# glove_final.net
KiCad netlist of a schematic drawn in EAGLE
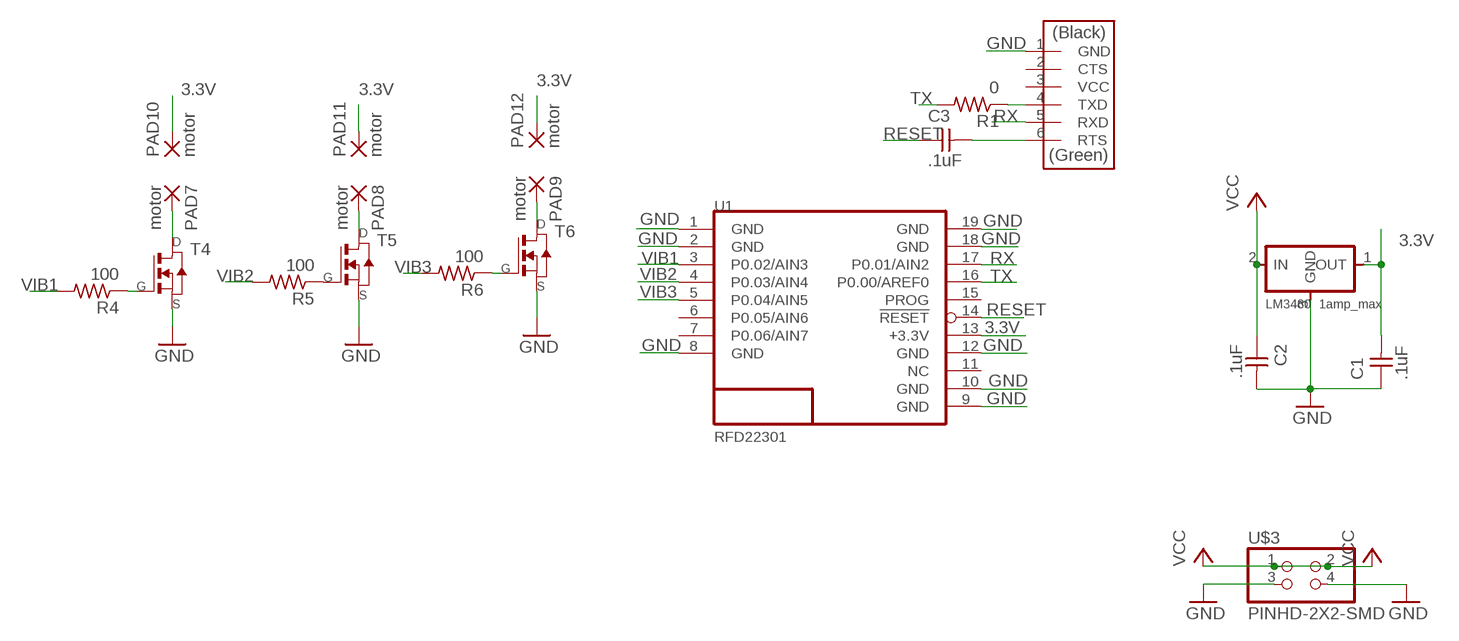
[diagram p0: schematic, sheet 1]

(export (version "E")
  (design (tool "Eeschema 10.0.6"))
  (components
    (comp (ref "C1")
      (value ".1uF")
      (footprint "eagle-import:C1206FAB")
      (libsource (lib "eagle-import") (part "CAP-UNPOLARIZEDFAB"))
    )
    (comp (ref "C2")
      (value ".1uF")
      (footprint "eagle-import:C1206FAB")
      (libsource (lib "eagle-import") (part "CAP-UNPOLARIZEDFAB"))
    )
    (comp (ref "C3")
      (value ".1uF")
      (footprint "eagle-import:C1206FAB")
      (libsource (lib "eagle-import") (part "CAP-UNPOLARIZEDFAB"))
    )
    (comp (ref "LM3480")
      (value "1amp_max")
      (footprint "eagle-import:SOT23")
      (libsource (lib "eagle-import") (part "REGULATORSOT23"))
    )
    (comp (ref "PAD7")
      (value "motor")
      (footprint "eagle-import:SMD1,27-2,54")
      (libsource (lib "eagle-import") (part "WIREPADSMD1,27-254"))
    )
    (comp (ref "PAD8")
      (value "motor")
      (footprint "eagle-import:SMD1,27-2,54")
      (libsource (lib "eagle-import") (part "WIREPADSMD1,27-254"))
    )
    (comp (ref "PAD9")
      (value "motor")
      (footprint "eagle-import:SMD1,27-2,54")
      (libsource (lib "eagle-import") (part "WIREPADSMD1,27-254"))
    )
    (comp (ref "PAD10")
      (value "motor")
      (footprint "eagle-import:SMD1,27-2,54")
      (libsource (lib "eagle-import") (part "WIREPADSMD1,27-254"))
    )
    (comp (ref "PAD11")
      (value "motor")
      (footprint "eagle-import:SMD1,27-2,54")
      (libsource (lib "eagle-import") (part "WIREPADSMD1,27-254"))
    )
    (comp (ref "PAD12")
      (value "motor")
      (footprint "eagle-import:SMD1,27-2,54")
      (libsource (lib "eagle-import") (part "WIREPADSMD1,27-254"))
    )
    (comp (ref "R1")
      (value "0")
      (footprint "eagle-import:R1206FAB")
      (libsource (lib "eagle-import") (part "RES-US1206FAB"))
    )
    (comp (ref "R4")
      (value "100")
      (footprint "eagle-import:R1206FAB")
      (libsource (lib "eagle-import") (part "RES-US1206FAB"))
    )
    (comp (ref "R5")
      (value "100")
      (footprint "eagle-import:R1206FAB")
      (libsource (lib "eagle-import") (part "RES-US1206FAB"))
    )
    (comp (ref "R6")
      (value "100")
      (footprint "eagle-import:R1206FAB")
      (libsource (lib "eagle-import") (part "RES-US1206FAB"))
    )
    (comp (ref "T4")
      (value "NMOSFETSOT23")
      (footprint "eagle-import:SOT-23")
      (libsource (lib "eagle-import") (part "NMOSFETSOT23"))
    )
    (comp (ref "T5")
      (value "NMOSFETSOT23")
      (footprint "eagle-import:SOT-23")
      (libsource (lib "eagle-import") (part "NMOSFETSOT23"))
    )
    (comp (ref "T6")
      (value "NMOSFETSOT23")
      (footprint "eagle-import:SOT-23")
      (libsource (lib "eagle-import") (part "NMOSFETSOT23"))
    )
    (comp (ref "U$1")
      (value "FTDI-SMD-HEADER")
      (footprint "eagle-import:1X06SMD")
      (libsource (lib "eagle-import") (part "FTDI-SMD-HEADER"))
    )
    (comp (ref "U$3")
      (value "PINHD-2X2-SMD")
      (footprint "eagle-import:2X02SMD")
      (libsource (lib "eagle-import") (part "PINHD-2X2-SMD"))
    )
    (comp (ref "U1")
      (value "RFD22301")
      (footprint "eagle-import:RFD22301")
      (libsource (lib "eagle-import") (part "RFD22301"))
    )
  )
  (nets
    (net (code "1") (name "/3.3V") (class "Default")
      (node (ref "C1") (pin "2") (pinfunction "2_2") (pintype "passive"))
      (node (ref "LM3480") (pin "1") (pinfunction "OUT_1") (pintype "bidirectional"))
      (node (ref "PAD10") (pin "1") (pinfunction "P_1") (pintype "passive"))
      (node (ref "PAD11") (pin "1") (pinfunction "P_1") (pintype "passive"))
      (node (ref "PAD12") (pin "1") (pinfunction "P_1") (pintype "passive"))
      (node (ref "U1") (pin "13") (pinfunction "+3.3V_13") (pintype "bidirectional"))
    )
    (net (code "2") (name "/RESET") (class "Default")
      (node (ref "C3") (pin "1") (pinfunction "1_1") (pintype "passive"))
      (node (ref "U1") (pin "14") (pinfunction "~{RESET}_14") (pintype "bidirectional"))
    )
    (net (code "3") (name "/RX") (class "Default")
      (node (ref "U$1") (pin "5") (pinfunction "RXD_5") (pintype "bidirectional"))
      (node (ref "U1") (pin "17") (pinfunction "P0.01/AIN2_17") (pintype "bidirectional"))
    )
    (net (code "4") (name "/TX") (class "Default")
      (node (ref "R1") (pin "2") (pinfunction "2_2") (pintype "passive"))
      (node (ref "U1") (pin "16") (pinfunction "P0.00/AREF0_16") (pintype "bidirectional"))
    )
    (net (code "5") (name "/VIB1") (class "Default")
      (node (ref "R4") (pin "2") (pinfunction "2_2") (pintype "passive"))
      (node (ref "U1") (pin "3") (pinfunction "P0.02/AIN3_3") (pintype "bidirectional"))
    )
    (net (code "6") (name "/VIB2") (class "Default")
      (node (ref "R5") (pin "2") (pinfunction "2_2") (pintype "passive"))
      (node (ref "U1") (pin "4") (pinfunction "P0.03/AIN4_4") (pintype "bidirectional"))
    )
    (net (code "7") (name "/VIB3") (class "Default")
      (node (ref "R6") (pin "2") (pinfunction "2_2") (pintype "passive"))
      (node (ref "U1") (pin "5") (pinfunction "P0.04/AIN5_5") (pintype "bidirectional"))
    )
    (net (code "8") (name "GND") (class "Default")
      (node (ref "C1") (pin "1") (pinfunction "1_1") (pintype "passive"))
      (node (ref "C2") (pin "2") (pinfunction "2_2") (pintype "passive"))
      (node (ref "LM3480") (pin "3") (pinfunction "GND_3") (pintype "bidirectional"))
      (node (ref "T4") (pin "2") (pinfunction "S_2") (pintype "passive"))
      (node (ref "T5") (pin "2") (pinfunction "S_2") (pintype "passive"))
      (node (ref "T6") (pin "2") (pinfunction "S_2") (pintype "passive"))
      (node (ref "U$1") (pin "1") (pinfunction "GND_1") (pintype "bidirectional"))
      (node (ref "U$3") (pin "3") (pinfunction "3_3") (pintype "passive"))
      (node (ref "U$3") (pin "4") (pinfunction "4_4") (pintype "passive"))
      (node (ref "U1") (pin "1") (pinfunction "GND_1") (pintype "bidirectional"))
      (node (ref "U1") (pin "10") (pinfunction "GND_10") (pintype "bidirectional"))
      (node (ref "U1") (pin "12") (pinfunction "GND_12") (pintype "bidirectional"))
      (node (ref "U1") (pin "18") (pinfunction "GND_18") (pintype "bidirectional"))
      (node (ref "U1") (pin "19") (pinfunction "GND_19") (pintype "bidirectional"))
      (node (ref "U1") (pin "2") (pinfunction "GND_2") (pintype "bidirectional"))
      (node (ref "U1") (pin "8") (pinfunction "GND_8") (pintype "bidirectional"))
      (node (ref "U1") (pin "9") (pinfunction "GND_9") (pintype "bidirectional"))
    )
    (net (code "9") (name "Net-(PAD7-P)") (class "Default")
      (node (ref "PAD7") (pin "1") (pinfunction "P_1") (pintype "passive"))
      (node (ref "T4") (pin "1") (pinfunction "D_1") (pintype "passive"))
    )
    (net (code "10") (name "Net-(PAD8-P)") (class "Default")
      (node (ref "PAD8") (pin "1") (pinfunction "P_1") (pintype "passive"))
      (node (ref "T5") (pin "1") (pinfunction "D_1") (pintype "passive"))
    )
    (net (code "11") (name "Net-(PAD9-P)") (class "Default")
      (node (ref "PAD9") (pin "1") (pinfunction "P_1") (pintype "passive"))
      (node (ref "T6") (pin "1") (pinfunction "D_1") (pintype "passive"))
    )
    (net (code "12") (name "Net-(T4-G)") (class "Default")
      (node (ref "R4") (pin "1") (pinfunction "1_1") (pintype "passive"))
      (node (ref "T4") (pin "3") (pinfunction "G_3") (pintype "passive"))
    )
    (net (code "13") (name "Net-(T5-G)") (class "Default")
      (node (ref "R5") (pin "1") (pinfunction "1_1") (pintype "passive"))
      (node (ref "T5") (pin "3") (pinfunction "G_3") (pintype "passive"))
    )
    (net (code "14") (name "Net-(T6-G)") (class "Default")
      (node (ref "R6") (pin "1") (pinfunction "1_1") (pintype "passive"))
      (node (ref "T6") (pin "3") (pinfunction "G_3") (pintype "passive"))
    )
    (net (code "15") (name "Net-(U$1-RTS)") (class "Default")
      (node (ref "C3") (pin "2") (pinfunction "2_2") (pintype "passive"))
      (node (ref "U$1") (pin "6") (pinfunction "RTS_6") (pintype "bidirectional"))
    )
    (net (code "16") (name "Net-(U$1-TXD)") (class "Default")
      (node (ref "R1") (pin "1") (pinfunction "1_1") (pintype "passive"))
      (node (ref "U$1") (pin "4") (pinfunction "TXD_4") (pintype "bidirectional"))
    )
    (net (code "17") (name "VCC") (class "Default")
      (node (ref "C2") (pin "1") (pinfunction "1_1") (pintype "passive"))
      (node (ref "LM3480") (pin "2") (pinfunction "IN_2") (pintype "bidirectional"))
      (node (ref "U$3") (pin "1") (pinfunction "1_1") (pintype "passive"))
      (node (ref "U$3") (pin "2") (pinfunction "2_2") (pintype "passive"))
    )
    (net (code "18") (name "unconnected-(U$1-CTS-Pad2)") (class "Default")
      (node (ref "U$1") (pin "2") (pinfunction "CTS_2") (pintype "bidirectional"))
    )
    (net (code "19") (name "unconnected-(U$1-VCC-Pad3)") (class "Default")
      (node (ref "U$1") (pin "3") (pinfunction "VCC_3") (pintype "bidirectional"))
    )
    (net (code "20") (name "unconnected-(U1-NC-Pad11)") (class "Default")
      (node (ref "U1") (pin "11") (pinfunction "NC_11") (pintype "no_connect"))
    )
    (net (code "21") (name "unconnected-(U1-P0.05{slash}AIN6-Pad6)") (class "Default")
      (node (ref "U1") (pin "6") (pinfunction "P0.05/AIN6_6") (pintype "bidirectional"))
    )
    (net (code "22") (name "unconnected-(U1-P0.06{slash}AIN7-Pad7)") (class "Default")
      (node (ref "U1") (pin "7") (pinfunction "P0.06/AIN7_7") (pintype "bidirectional"))
    )
    (net (code "23") (name "unconnected-(U1-PROG-Pad15)") (class "Default")
      (node (ref "U1") (pin "15") (pinfunction "PROG_15") (pintype "bidirectional"))
    )
  )
)
